# Driver_Controls_Board_v1_4.net
KiCad netlist of a schematic drawn in EAGLE
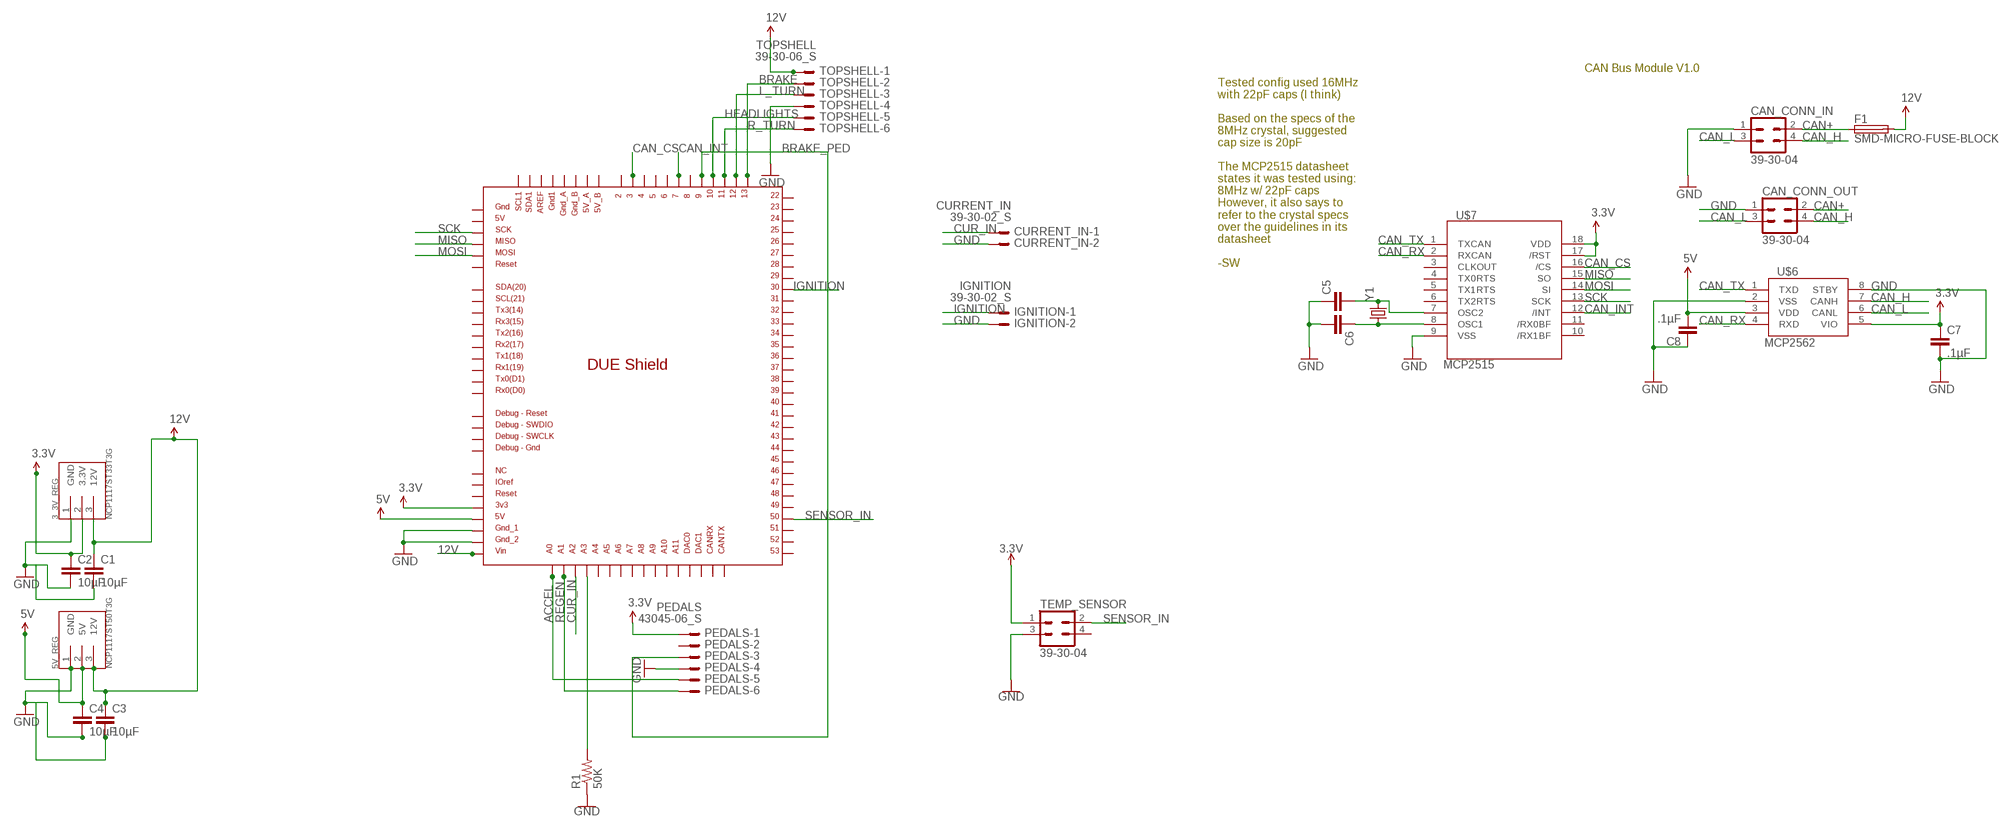
[diagram p0: schematic, sheet 1]

(export (version "E")
  (design (tool "Eeschema 10.0.6"))
  (components
    (comp (ref "3_3V_REG")
      (value "NCP1117ST33T3G")
      (footprint "eagle-import:SOT223")
      (libsource (lib "eagle-import") (part "NCP1117ST33T3G"))
    )
    (comp (ref "5V_REG")
      (value "NCP1117ST50T3G")
      (footprint "eagle-import:SOT223")
      (libsource (lib "eagle-import") (part "NCP1117ST50T3G"))
    )
    (comp (ref "C1")
      (value "10µF")
      (footprint "eagle-import:0805")
      (libsource (lib "eagle-import") (part "CAP0805"))
    )
    (comp (ref "C2")
      (value "10µF")
      (footprint "eagle-import:0805")
      (libsource (lib "eagle-import") (part "CAP0805"))
    )
    (comp (ref "C3")
      (value "10µF")
      (footprint "eagle-import:0805")
      (libsource (lib "eagle-import") (part "CAP0805"))
    )
    (comp (ref "C4")
      (value "10µF")
      (footprint "eagle-import:0805")
      (libsource (lib "eagle-import") (part "CAP0805"))
    )
    (comp (ref "C5")
      (value "CAP0805")
      (footprint "eagle-import:0805")
      (libsource (lib "eagle-import") (part "CAP0805"))
    )
    (comp (ref "C6")
      (value "CAP0805")
      (footprint "eagle-import:0805")
      (libsource (lib "eagle-import") (part "CAP0805"))
    )
    (comp (ref "C7")
      (value ".1µF")
      (footprint "eagle-import:0805")
      (libsource (lib "eagle-import") (part "CAP0805"))
    )
    (comp (ref "C8")
      (value ".1µF")
      (footprint "eagle-import:0805")
      (libsource (lib "eagle-import") (part "CAP0805"))
    )
    (comp (ref "CAN_CONN_IN")
      (value "39-30-04")
      (footprint "eagle-import:39-30-_04_")
      (libsource (lib "eagle-import") (part "39-30-?04?"))
    )
    (comp (ref "CAN_CONN_OUT")
      (value "39-30-04")
      (footprint "eagle-import:39-30-_04_")
      (libsource (lib "eagle-import") (part "39-30-?04?"))
    )
    (comp (ref "CURRENT_IN")
      (value "39-30-02_S")
      (footprint "eagle-import:39-30-_02_")
      (libsource (lib "eagle-import") (part "39-30-?02?_S"))
    )
    (comp (ref "F1")
      (value "SMD-MICRO-FUSE-BLOCK")
      (footprint "eagle-import:OMNIBLOK")
      (libsource (lib "eagle-import") (part "SMD-MICRO-FUSE-BLOCK"))
    )
    (comp (ref "IGNITION")
      (value "39-30-02_S")
      (footprint "eagle-import:39-30-_02_")
      (libsource (lib "eagle-import") (part "39-30-?02?_S"))
    )
    (comp (ref "PEDALS")
      (value "43045-06_S")
      (footprint "eagle-import:43045-06")
      (libsource (lib "eagle-import") (part "43045-06_S"))
    )
    (comp (ref "R1")
      (value "50K")
      (footprint "eagle-import:VTA55")
      (libsource (lib "eagle-import") (part "R-US_VTA55"))
    )
    (comp (ref "TEMP_SENSOR")
      (value "39-30-04")
      (footprint "eagle-import:39-30-_04_")
      (libsource (lib "eagle-import") (part "39-30-?04?"))
    )
    (comp (ref "TOPSHELL")
      (value "39-30-06_S")
      (footprint "eagle-import:39-30-_06_")
      (libsource (lib "eagle-import") (part "39-30-?06?_S"))
    )
    (comp (ref "U$2")
      (value "DUE(NORMAL)")
      (footprint "eagle-import:DUE(NORMAL)")
      (libsource (lib "eagle-import") (part "DUE(NORMAL)"))
    )
    (comp (ref "U$6")
      (value "MCP2562")
      (footprint "eagle-import:SOIC8")
      (libsource (lib "eagle-import") (part "MCP2562"))
    )
    (comp (ref "U$7")
      (value "MCP2515")
      (footprint "eagle-import:SO-18W")
      (libsource (lib "eagle-import") (part "MCP2515"))
    )
    (comp (ref "Y1")
      (value "CRYSTALHC49US")
      (footprint "eagle-import:HC49US")
      (libsource (lib "eagle-import") (part "CRYSTALHC49US"))
    )
  )
  (nets
    (net (code "1") (name "/ACCEL") (class "Default")
      (node (ref "PEDALS") (pin "5") (pinfunction "P_5") (pintype "passive"))
      (node (ref "U$2") (pin "A0") (pinfunction "A0_A0") (pintype "bidirectional"))
    )
    (net (code "2") (name "/BRAKE") (class "Default")
      (node (ref "TOPSHELL") (pin "2") (pinfunction "P_2") (pintype "passive"))
      (node (ref "U$2") (pin "13") (pinfunction "13_13") (pintype "bidirectional"))
    )
    (net (code "3") (name "/BRAKE_PED") (class "Default")
      (node (ref "PEDALS") (pin "3") (pinfunction "P_3") (pintype "passive"))
      (node (ref "U$2") (pin "9") (pinfunction "9_9") (pintype "bidirectional"))
    )
    (net (code "4") (name "/CAN+") (class "Default")
      (node (ref "CAN_CONN_IN") (pin "2") (pinfunction "2_2") (pintype "passive"))
      (node (ref "CAN_CONN_OUT") (pin "2") (pinfunction "2_2") (pintype "passive"))
      (node (ref "F1") (pin "P$1") (pinfunction "1_P$1") (pintype "passive"))
    )
    (net (code "5") (name "/CAN_CS") (class "Default")
      (node (ref "U$2") (pin "3") (pinfunction "3_3") (pintype "bidirectional"))
      (node (ref "U$7") (pin "16") (pinfunction "/CS_16") (pintype "bidirectional"))
    )
    (net (code "6") (name "/CAN_H") (class "Default")
      (node (ref "CAN_CONN_IN") (pin "4") (pinfunction "4_4") (pintype "passive"))
      (node (ref "CAN_CONN_OUT") (pin "4") (pinfunction "4_4") (pintype "passive"))
      (node (ref "U$6") (pin "7") (pinfunction "CANH_7") (pintype "bidirectional"))
    )
    (net (code "7") (name "/CAN_INT") (class "Default")
      (node (ref "U$2") (pin "7") (pinfunction "7_7") (pintype "bidirectional"))
      (node (ref "U$7") (pin "12") (pinfunction "/INT_12") (pintype "bidirectional"))
    )
    (net (code "8") (name "/CAN_L") (class "Default")
      (node (ref "CAN_CONN_IN") (pin "3") (pinfunction "3_3") (pintype "passive"))
      (node (ref "CAN_CONN_OUT") (pin "3") (pinfunction "3_3") (pintype "passive"))
      (node (ref "U$6") (pin "6") (pinfunction "CANL_6") (pintype "bidirectional"))
    )
    (net (code "9") (name "/CAN_RX") (class "Default")
      (node (ref "U$6") (pin "4") (pinfunction "RXD_4") (pintype "bidirectional"))
      (node (ref "U$7") (pin "2") (pinfunction "RXCAN_2") (pintype "bidirectional"))
    )
    (net (code "10") (name "/CAN_TX") (class "Default")
      (node (ref "U$6") (pin "1") (pinfunction "TXD_1") (pintype "bidirectional"))
      (node (ref "U$7") (pin "1") (pinfunction "TXCAN_1") (pintype "bidirectional"))
    )
    (net (code "11") (name "/CUR_IN") (class "Default")
      (node (ref "CURRENT_IN") (pin "1") (pinfunction "P_1") (pintype "passive"))
      (node (ref "U$2") (pin "A2") (pinfunction "A2_A2") (pintype "bidirectional"))
    )
    (net (code "12") (name "/HEADLIGHTS") (class "Default")
      (node (ref "TOPSHELL") (pin "5") (pinfunction "P_5") (pintype "passive"))
      (node (ref "U$2") (pin "10") (pinfunction "10_10") (pintype "bidirectional"))
    )
    (net (code "13") (name "/IGNITION") (class "Default")
      (node (ref "IGNITION") (pin "1") (pinfunction "P_1") (pintype "passive"))
      (node (ref "U$2") (pin "30") (pinfunction "30_30") (pintype "bidirectional"))
    )
    (net (code "14") (name "/L_TURN") (class "Default")
      (node (ref "TOPSHELL") (pin "3") (pinfunction "P_3") (pintype "passive"))
      (node (ref "U$2") (pin "12") (pinfunction "12_12") (pintype "bidirectional"))
    )
    (net (code "15") (name "/MISO") (class "Default")
      (node (ref "U$2") (pin "MISO_ICSP") (pinfunction "MISO_ICSP_MISO_ICSP") (pintype "bidirectional"))
      (node (ref "U$7") (pin "15") (pinfunction "SO_15") (pintype "bidirectional"))
    )
    (net (code "16") (name "/MOSI") (class "Default")
      (node (ref "U$2") (pin "MOSI_ICSP") (pinfunction "MOSI_ICSP_MOSI_ICSP") (pintype "bidirectional"))
      (node (ref "U$7") (pin "14") (pinfunction "SI_14") (pintype "bidirectional"))
    )
    (net (code "17") (name "/REGEN") (class "Default")
      (node (ref "PEDALS") (pin "6") (pinfunction "P_6") (pintype "passive"))
      (node (ref "U$2") (pin "A1") (pinfunction "A1_A1") (pintype "bidirectional"))
    )
    (net (code "18") (name "/R_TURN") (class "Default")
      (node (ref "TOPSHELL") (pin "6") (pinfunction "P_6") (pintype "passive"))
      (node (ref "U$2") (pin "11") (pinfunction "11_11") (pintype "bidirectional"))
    )
    (net (code "19") (name "/SCK") (class "Default")
      (node (ref "U$2") (pin "SCK_ICSP") (pinfunction "SCK_ICSP_SCK_ICSP") (pintype "bidirectional"))
      (node (ref "U$7") (pin "13") (pinfunction "SCK_13") (pintype "bidirectional"))
    )
    (net (code "20") (name "/SENSOR_IN") (class "Default")
      (node (ref "TEMP_SENSOR") (pin "2") (pinfunction "2_2") (pintype "passive"))
      (node (ref "U$2") (pin "50") (pinfunction "50_50") (pintype "bidirectional"))
    )
    (net (code "21") (name "3.3V") (class "Default")
      (node (ref "3_3V_REG") (pin "2") (pinfunction "3.3V_2") (pintype "bidirectional"))
      (node (ref "C2") (pin "1") (pinfunction "1_1") (pintype "passive"))
      (node (ref "C7") (pin "1") (pinfunction "1_1") (pintype "passive"))
      (node (ref "PEDALS") (pin "1") (pinfunction "P_1") (pintype "passive"))
      (node (ref "TEMP_SENSOR") (pin "1") (pinfunction "1_1") (pintype "passive"))
      (node (ref "U$2") (pin "3V3") (pinfunction "3V3_3V3") (pintype "bidirectional"))
      (node (ref "U$6") (pin "5") (pinfunction "VIO_5") (pintype "bidirectional"))
      (node (ref "U$7") (pin "17") (pinfunction "/RST_17") (pintype "bidirectional"))
      (node (ref "U$7") (pin "18") (pinfunction "VDD_18") (pintype "bidirectional"))
    )
    (net (code "22") (name "5V") (class "Default")
      (node (ref "5V_REG") (pin "2") (pinfunction "5V_2") (pintype "bidirectional"))
      (node (ref "C4") (pin "1") (pinfunction "1_1") (pintype "passive"))
      (node (ref "C8") (pin "2") (pinfunction "2_2") (pintype "passive"))
      (node (ref "U$2") (pin "5V") (pinfunction "5V_5V") (pintype "bidirectional"))
      (node (ref "U$6") (pin "3") (pinfunction "VDD_3") (pintype "bidirectional"))
    )
    (net (code "23") (name "12V") (class "Default")
      (node (ref "3_3V_REG") (pin "3") (pinfunction "12V_3") (pintype "bidirectional"))
      (node (ref "5V_REG") (pin "3") (pinfunction "12V_3") (pintype "bidirectional"))
      (node (ref "C1") (pin "1") (pinfunction "1_1") (pintype "passive"))
      (node (ref "C3") (pin "1") (pinfunction "1_1") (pintype "passive"))
      (node (ref "F1") (pin "P$2") (pinfunction "2_P$2") (pintype "passive"))
      (node (ref "TOPSHELL") (pin "1") (pinfunction "P_1") (pintype "passive"))
      (node (ref "U$2") (pin "VIN") (pinfunction "VIN_VIN") (pintype "bidirectional"))
    )
    (net (code "24") (name "GND") (class "Default")
      (node (ref "3_3V_REG") (pin "1") (pinfunction "GND_1") (pintype "bidirectional"))
      (node (ref "5V_REG") (pin "1") (pinfunction "GND_1") (pintype "bidirectional"))
      (node (ref "C1") (pin "2") (pinfunction "2_2") (pintype "passive"))
      (node (ref "C2") (pin "2") (pinfunction "2_2") (pintype "passive"))
      (node (ref "C3") (pin "2") (pinfunction "2_2") (pintype "passive"))
      (node (ref "C4") (pin "2") (pinfunction "2_2") (pintype "passive"))
      (node (ref "C5") (pin "1") (pinfunction "1_1") (pintype "passive"))
      (node (ref "C6") (pin "2") (pinfunction "2_2") (pintype "passive"))
      (node (ref "C7") (pin "2") (pinfunction "2_2") (pintype "passive"))
      (node (ref "C8") (pin "1") (pinfunction "1_1") (pintype "passive"))
      (node (ref "CAN_CONN_IN") (pin "1") (pinfunction "1_1") (pintype "passive"))
      (node (ref "CAN_CONN_OUT") (pin "1") (pinfunction "1_1") (pintype "passive"))
      (node (ref "CURRENT_IN") (pin "2") (pinfunction "P_2") (pintype "passive"))
      (node (ref "IGNITION") (pin "2") (pinfunction "P_2") (pintype "passive"))
      (node (ref "PEDALS") (pin "4") (pinfunction "P_4") (pintype "passive"))
      (node (ref "R1") (pin "1") (pinfunction "1_1") (pintype "passive"))
      (node (ref "TEMP_SENSOR") (pin "3") (pinfunction "3_3") (pintype "passive"))
      (node (ref "TOPSHELL") (pin "4") (pinfunction "P_4") (pintype "passive"))
      (node (ref "U$2") (pin "GND_1") (pinfunction "GND_1_GND_1") (pintype "bidirectional"))
      (node (ref "U$2") (pin "GND_2") (pinfunction "GND_2_GND_2") (pintype "bidirectional"))
      (node (ref "U$6") (pin "2") (pinfunction "VSS_2") (pintype "bidirectional"))
      (node (ref "U$6") (pin "8") (pinfunction "STBY_8") (pintype "bidirectional"))
      (node (ref "U$7") (pin "9") (pinfunction "VSS_9") (pintype "bidirectional"))
    )
    (net (code "25") (name "Net-(R1-Pad2)") (class "Default")
      (node (ref "R1") (pin "2") (pinfunction "2_2") (pintype "passive"))
      (node (ref "U$2") (pin "A3") (pinfunction "A3_A3") (pintype "bidirectional"))
    )
    (net (code "26") (name "Net-(U$7-OSC1)") (class "Default")
      (node (ref "C6") (pin "1") (pinfunction "1_1") (pintype "passive"))
      (node (ref "U$7") (pin "8") (pinfunction "OSC1_8") (pintype "bidirectional"))
      (node (ref "Y1") (pin "1") (pinfunction "1_1") (pintype "passive"))
    )
    (net (code "27") (name "Net-(U$7-OSC2)") (class "Default")
      (node (ref "C5") (pin "2") (pinfunction "2_2") (pintype "passive"))
      (node (ref "U$7") (pin "7") (pinfunction "OSC2_7") (pintype "bidirectional"))
      (node (ref "Y1") (pin "2") (pinfunction "2_2") (pintype "passive"))
    )
    (net (code "28") (name "unconnected-(PEDALSB-P-Pad2)") (class "Default")
      (node (ref "PEDALS") (pin "2") (pinfunction "P_2") (pintype "passive"))
    )
    (net (code "29") (name "unconnected-(TEMP_SENSOR-Pad4)") (class "Default")
      (node (ref "TEMP_SENSOR") (pin "4") (pinfunction "4_4") (pintype "passive"))
    )
    (net (code "30") (name "unconnected-(U$2-Pad2)") (class "Default")
      (node (ref "U$2") (pin "2") (pinfunction "2_2") (pintype "bidirectional"))
    )
    (net (code "31") (name "unconnected-(U$2-Pad4)") (class "Default")
      (node (ref "U$2") (pin "4") (pinfunction "4_4") (pintype "bidirectional"))
    )
    (net (code "32") (name "unconnected-(U$2-Pad5)") (class "Default")
      (node (ref "U$2") (pin "5") (pinfunction "5_5") (pintype "bidirectional"))
    )
    (net (code "33") (name "unconnected-(U$2-Pad5V_A)") (class "Default")
      (node (ref "U$2") (pin "5V_A") (pinfunction "5V_A_5V_A") (pintype "bidirectional"))
    )
    (net (code "34") (name "unconnected-(U$2-Pad5V_B)") (class "Default")
      (node (ref "U$2") (pin "5V_B") (pinfunction "5V_B_5V_B") (pintype "bidirectional"))
    )
    (net (code "35") (name "unconnected-(U$2-Pad5V_ICSP)") (class "Default")
      (node (ref "U$2") (pin "5V_ICSP") (pinfunction "5V_ICSP_5V_ICSP") (pintype "bidirectional"))
    )
    (net (code "36") (name "unconnected-(U$2-Pad6)") (class "Default")
      (node (ref "U$2") (pin "6") (pinfunction "6_6") (pintype "bidirectional"))
    )
    (net (code "37") (name "unconnected-(U$2-Pad8)") (class "Default")
      (node (ref "U$2") (pin "8") (pinfunction "8_8") (pintype "bidirectional"))
    )
    (net (code "38") (name "unconnected-(U$2-Pad22)") (class "Default")
      (node (ref "U$2") (pin "22") (pinfunction "22_22") (pintype "bidirectional"))
    )
    (net (code "39") (name "unconnected-(U$2-Pad23)") (class "Default")
      (node (ref "U$2") (pin "23") (pinfunction "23_23") (pintype "bidirectional"))
    )
    (net (code "40") (name "unconnected-(U$2-Pad24)") (class "Default")
      (node (ref "U$2") (pin "24") (pinfunction "24_24") (pintype "bidirectional"))
    )
    (net (code "41") (name "unconnected-(U$2-Pad25)") (class "Default")
      (node (ref "U$2") (pin "25") (pinfunction "25_25") (pintype "bidirectional"))
    )
    (net (code "42") (name "unconnected-(U$2-Pad26)") (class "Default")
      (node (ref "U$2") (pin "26") (pinfunction "26_26") (pintype "bidirectional"))
    )
    (net (code "43") (name "unconnected-(U$2-Pad27)") (class "Default")
      (node (ref "U$2") (pin "27") (pinfunction "27_27") (pintype "bidirectional"))
    )
    (net (code "44") (name "unconnected-(U$2-Pad28)") (class "Default")
      (node (ref "U$2") (pin "28") (pinfunction "28_28") (pintype "bidirectional"))
    )
    (net (code "45") (name "unconnected-(U$2-Pad29)") (class "Default")
      (node (ref "U$2") (pin "29") (pinfunction "29_29") (pintype "bidirectional"))
    )
    (net (code "46") (name "unconnected-(U$2-Pad31)") (class "Default")
      (node (ref "U$2") (pin "31") (pinfunction "31_31") (pintype "bidirectional"))
    )
    (net (code "47") (name "unconnected-(U$2-Pad32)") (class "Default")
      (node (ref "U$2") (pin "32") (pinfunction "32_32") (pintype "bidirectional"))
    )
    (net (code "48") (name "unconnected-(U$2-Pad33)") (class "Default")
      (node (ref "U$2") (pin "33") (pinfunction "33_33") (pintype "bidirectional"))
    )
    (net (code "49") (name "unconnected-(U$2-Pad34)") (class "Default")
      (node (ref "U$2") (pin "34") (pinfunction "34_34") (pintype "bidirectional"))
    )
    (net (code "50") (name "unconnected-(U$2-Pad35)") (class "Default")
      (node (ref "U$2") (pin "35") (pinfunction "35_35") (pintype "bidirectional"))
    )
    (net (code "51") (name "unconnected-(U$2-Pad36)") (class "Default")
      (node (ref "U$2") (pin "36") (pinfunction "36_36") (pintype "bidirectional"))
    )
    (net (code "52") (name "unconnected-(U$2-Pad37)") (class "Default")
      (node (ref "U$2") (pin "37") (pinfunction "37_37") (pintype "bidirectional"))
    )
    (net (code "53") (name "unconnected-(U$2-Pad38)") (class "Default")
      (node (ref "U$2") (pin "38") (pinfunction "38_38") (pintype "bidirectional"))
    )
    (net (code "54") (name "unconnected-(U$2-Pad39)") (class "Default")
      (node (ref "U$2") (pin "39") (pinfunction "39_39") (pintype "bidirectional"))
    )
    (net (code "55") (name "unconnected-(U$2-Pad40)") (class "Default")
      (node (ref "U$2") (pin "40") (pinfunction "40_40") (pintype "bidirectional"))
    )
    (net (code "56") (name "unconnected-(U$2-Pad41)") (class "Default")
      (node (ref "U$2") (pin "41") (pinfunction "41_41") (pintype "bidirectional"))
    )
    (net (code "57") (name "unconnected-(U$2-Pad42)") (class "Default")
      (node (ref "U$2") (pin "42") (pinfunction "42_42") (pintype "bidirectional"))
    )
    (net (code "58") (name "unconnected-(U$2-Pad43)") (class "Default")
      (node (ref "U$2") (pin "43") (pinfunction "43_43") (pintype "bidirectional"))
    )
    (net (code "59") (name "unconnected-(U$2-Pad44)") (class "Default")
      (node (ref "U$2") (pin "44") (pinfunction "44_44") (pintype "bidirectional"))
    )
    (net (code "60") (name "unconnected-(U$2-Pad45)") (class "Default")
      (node (ref "U$2") (pin "45") (pinfunction "45_45") (pintype "bidirectional"))
    )
    (net (code "61") (name "unconnected-(U$2-Pad46)") (class "Default")
      (node (ref "U$2") (pin "46") (pinfunction "46_46") (pintype "bidirectional"))
    )
    (net (code "62") (name "unconnected-(U$2-Pad47)") (class "Default")
      (node (ref "U$2") (pin "47") (pinfunction "47_47") (pintype "bidirectional"))
    )
    (net (code "63") (name "unconnected-(U$2-Pad48)") (class "Default")
      (node (ref "U$2") (pin "48") (pinfunction "48_48") (pintype "bidirectional"))
    )
    (net (code "64") (name "unconnected-(U$2-Pad49)") (class "Default")
      (node (ref "U$2") (pin "49") (pinfunction "49_49") (pintype "bidirectional"))
    )
    (net (code "65") (name "unconnected-(U$2-Pad51)") (class "Default")
      (node (ref "U$2") (pin "51") (pinfunction "51_51") (pintype "bidirectional"))
    )
    (net (code "66") (name "unconnected-(U$2-Pad52)") (class "Default")
      (node (ref "U$2") (pin "52") (pinfunction "52_52") (pintype "bidirectional"))
    )
    (net (code "67") (name "unconnected-(U$2-Pad53)") (class "Default")
      (node (ref "U$2") (pin "53") (pinfunction "53_53") (pintype "bidirectional"))
    )
    (net (code "68") (name "unconnected-(U$2-PadA4)") (class "Default")
      (node (ref "U$2") (pin "A4") (pinfunction "A4_A4") (pintype "bidirectional"))
    )
    (net (code "69") (name "unconnected-(U$2-PadA5)") (class "Default")
      (node (ref "U$2") (pin "A5") (pinfunction "A5_A5") (pintype "bidirectional"))
    )
    (net (code "70") (name "unconnected-(U$2-PadA6)") (class "Default")
      (node (ref "U$2") (pin "A6") (pinfunction "A6_A6") (pintype "bidirectional"))
    )
    (net (code "71") (name "unconnected-(U$2-PadA7)") (class "Default")
      (node (ref "U$2") (pin "A7") (pinfunction "A7_A7") (pintype "bidirectional"))
    )
    (net (code "72") (name "unconnected-(U$2-PadA8)") (class "Default")
      (node (ref "U$2") (pin "A8") (pinfunction "A8_A8") (pintype "bidirectional"))
    )
    (net (code "73") (name "unconnected-(U$2-PadA9)") (class "Default")
      (node (ref "U$2") (pin "A9") (pinfunction "A9_A9") (pintype "bidirectional"))
    )
    (net (code "74") (name "unconnected-(U$2-PadA10)") (class "Default")
      (node (ref "U$2") (pin "A10") (pinfunction "A10_A10") (pintype "bidirectional"))
    )
    (net (code "75") (name "unconnected-(U$2-PadA11)") (class "Default")
      (node (ref "U$2") (pin "A11") (pinfunction "A11_A11") (pintype "bidirectional"))
    )
    (net (code "76") (name "unconnected-(U$2-PadAREF)") (class "Default")
      (node (ref "U$2") (pin "AREF") (pinfunction "AREF_AREF") (pintype "bidirectional"))
    )
    (net (code "77") (name "unconnected-(U$2-PadCANRX)") (class "Default")
      (node (ref "U$2") (pin "CANRX") (pinfunction "CANRX_CANRX") (pintype "bidirectional"))
    )
    (net (code "78") (name "unconnected-(U$2-PadCANTX)") (class "Default")
      (node (ref "U$2") (pin "CANTX") (pinfunction "CANTX_CANTX") (pintype "bidirectional"))
    )
    (net (code "79") (name "unconnected-(U$2-PadDAC0)") (class "Default")
      (node (ref "U$2") (pin "DAC0") (pinfunction "DAC0_DAC0") (pintype "bidirectional"))
    )
    (net (code "80") (name "unconnected-(U$2-PadDAC1)") (class "Default")
      (node (ref "U$2") (pin "DAC1") (pinfunction "DAC1_DAC1") (pintype "bidirectional"))
    )
    (net (code "81") (name "unconnected-(U$2-PadGND1)") (class "Default")
      (node (ref "U$2") (pin "GND1") (pinfunction "GND1_GND1") (pintype "bidirectional"))
    )
    (net (code "82") (name "unconnected-(U$2-PadGND_A)") (class "Default")
      (node (ref "U$2") (pin "GND_A") (pinfunction "GND_A_GND_A") (pintype "bidirectional"))
    )
    (net (code "83") (name "unconnected-(U$2-PadGND_B)") (class "Default")
      (node (ref "U$2") (pin "GND_B") (pinfunction "GND_B_GND_B") (pintype "bidirectional"))
    )
    (net (code "84") (name "unconnected-(U$2-PadGND_DEBUG)") (class "Default")
      (node (ref "U$2") (pin "GND_DEBUG") (pinfunction "GND_DEBUG_GND_DEBUG") (pintype "bidirectional"))
    )
    (net (code "85") (name "unconnected-(U$2-PadGND_ICSP)") (class "Default")
      (node (ref "U$2") (pin "GND_ICSP") (pinfunction "GND_ICSP_GND_ICSP") (pintype "bidirectional"))
    )
    (net (code "86") (name "unconnected-(U$2-PadIOREF)") (class "Default")
      (node (ref "U$2") (pin "IOREF") (pinfunction "IOREF_IOREF") (pintype "bidirectional"))
    )
    (net (code "87") (name "unconnected-(U$2-PadNC)") (class "Default")
      (node (ref "U$2") (pin "NC") (pinfunction "NC_NC") (pintype "bidirectional"))
    )
    (net (code "88") (name "unconnected-(U$2-PadRESET)") (class "Default")
      (node (ref "U$2") (pin "RESET") (pinfunction "RESET_RESET") (pintype "bidirectional"))
    )
    (net (code "89") (name "unconnected-(U$2-PadRESET_DEBUG)") (class "Default")
      (node (ref "U$2") (pin "RESET_DEBUG") (pinfunction "RESET_DEBUG_RESET_DEBUG") (pintype "bidirectional"))
    )
    (net (code "90") (name "unconnected-(U$2-PadRESET_ICSP)") (class "Default")
      (node (ref "U$2") (pin "RESET_ICSP") (pinfunction "RESET_ICSP_RESET_ICSP") (pintype "bidirectional"))
    )
    (net (code "91") (name "unconnected-(U$2-PadRX0)") (class "Default")
      (node (ref "U$2") (pin "RX0") (pinfunction "RX0_RX0") (pintype "bidirectional"))
    )
    (net (code "92") (name "unconnected-(U$2-PadRX1)") (class "Default")
      (node (ref "U$2") (pin "RX1") (pinfunction "RX1_RX1") (pintype "bidirectional"))
    )
    (net (code "93") (name "unconnected-(U$2-PadRX2)") (class "Default")
      (node (ref "U$2") (pin "RX2") (pinfunction "RX2_RX2") (pintype "bidirectional"))
    )
    (net (code "94") (name "unconnected-(U$2-PadRX3)") (class "Default")
      (node (ref "U$2") (pin "RX3") (pinfunction "RX3_RX3") (pintype "bidirectional"))
    )
    (net (code "95") (name "unconnected-(U$2-PadSCL)") (class "Default")
      (node (ref "U$2") (pin "SCL") (pinfunction "SCL_SCL") (pintype "bidirectional"))
    )
    (net (code "96") (name "unconnected-(U$2-PadSCL1)") (class "Default")
      (node (ref "U$2") (pin "SCL1") (pinfunction "SCL1_SCL1") (pintype "bidirectional"))
    )
    (net (code "97") (name "unconnected-(U$2-PadSDA)") (class "Default")
      (node (ref "U$2") (pin "SDA") (pinfunction "SDA_SDA") (pintype "bidirectional"))
    )
    (net (code "98") (name "unconnected-(U$2-PadSDA1)") (class "Default")
      (node (ref "U$2") (pin "SDA1") (pinfunction "SDA1_SDA1") (pintype "bidirectional"))
    )
    (net (code "99") (name "unconnected-(U$2-PadSWCLK_DEBUG)") (class "Default")
      (node (ref "U$2") (pin "SWCLK_DEBUG") (pinfunction "SWCLK_DEBUG_SWCLK_DEBUG") (pintype "bidirectional"))
    )
    (net (code "100") (name "unconnected-(U$2-PadSWDIO_DEBUG)") (class "Default")
      (node (ref "U$2") (pin "SWDIO_DEBUG") (pinfunction "SWDIO_DEBUG_SWDIO_DEBUG") (pintype "bidirectional"))
    )
    (net (code "101") (name "unconnected-(U$2-PadTX0)") (class "Default")
      (node (ref "U$2") (pin "TX0") (pinfunction "TX0_TX0") (pintype "bidirectional"))
    )
    (net (code "102") (name "unconnected-(U$2-PadTX1)") (class "Default")
      (node (ref "U$2") (pin "TX1") (pinfunction "TX1_TX1") (pintype "bidirectional"))
    )
    (net (code "103") (name "unconnected-(U$2-PadTX2)") (class "Default")
      (node (ref "U$2") (pin "TX2") (pinfunction "TX2_TX2") (pintype "bidirectional"))
    )
    (net (code "104") (name "unconnected-(U$2-PadTX3)") (class "Default")
      (node (ref "U$2") (pin "TX3") (pinfunction "TX3_TX3") (pintype "bidirectional"))
    )
    (net (code "105") (name "unconnected-(U$7-CLKOUT-Pad3)") (class "Default")
      (node (ref "U$7") (pin "3") (pinfunction "CLKOUT_3") (pintype "bidirectional"))
    )
    (net (code "106") (name "unconnected-(U$7-TX0RTS-Pad4)") (class "Default")
      (node (ref "U$7") (pin "4") (pinfunction "TX0RTS_4") (pintype "bidirectional"))
    )
    (net (code "107") (name "unconnected-(U$7-TX1RTS-Pad5)") (class "Default")
      (node (ref "U$7") (pin "5") (pinfunction "TX1RTS_5") (pintype "bidirectional"))
    )
    (net (code "108") (name "unconnected-(U$7-TX2RTS-Pad6)") (class "Default")
      (node (ref "U$7") (pin "6") (pinfunction "TX2RTS_6") (pintype "bidirectional"))
    )
    (net (code "109") (name "unconnected-(U$7-{slash}RX0BF-Pad11)") (class "Default")
      (node (ref "U$7") (pin "11") (pinfunction "/RX0BF_11") (pintype "bidirectional"))
    )
    (net (code "110") (name "unconnected-(U$7-{slash}RX1BF-Pad10)") (class "Default")
      (node (ref "U$7") (pin "10") (pinfunction "/RX1BF_10") (pintype "bidirectional"))
    )
  )
)
